# USB-Isolator_v11.net
KiCad netlist of a schematic drawn in EAGLE
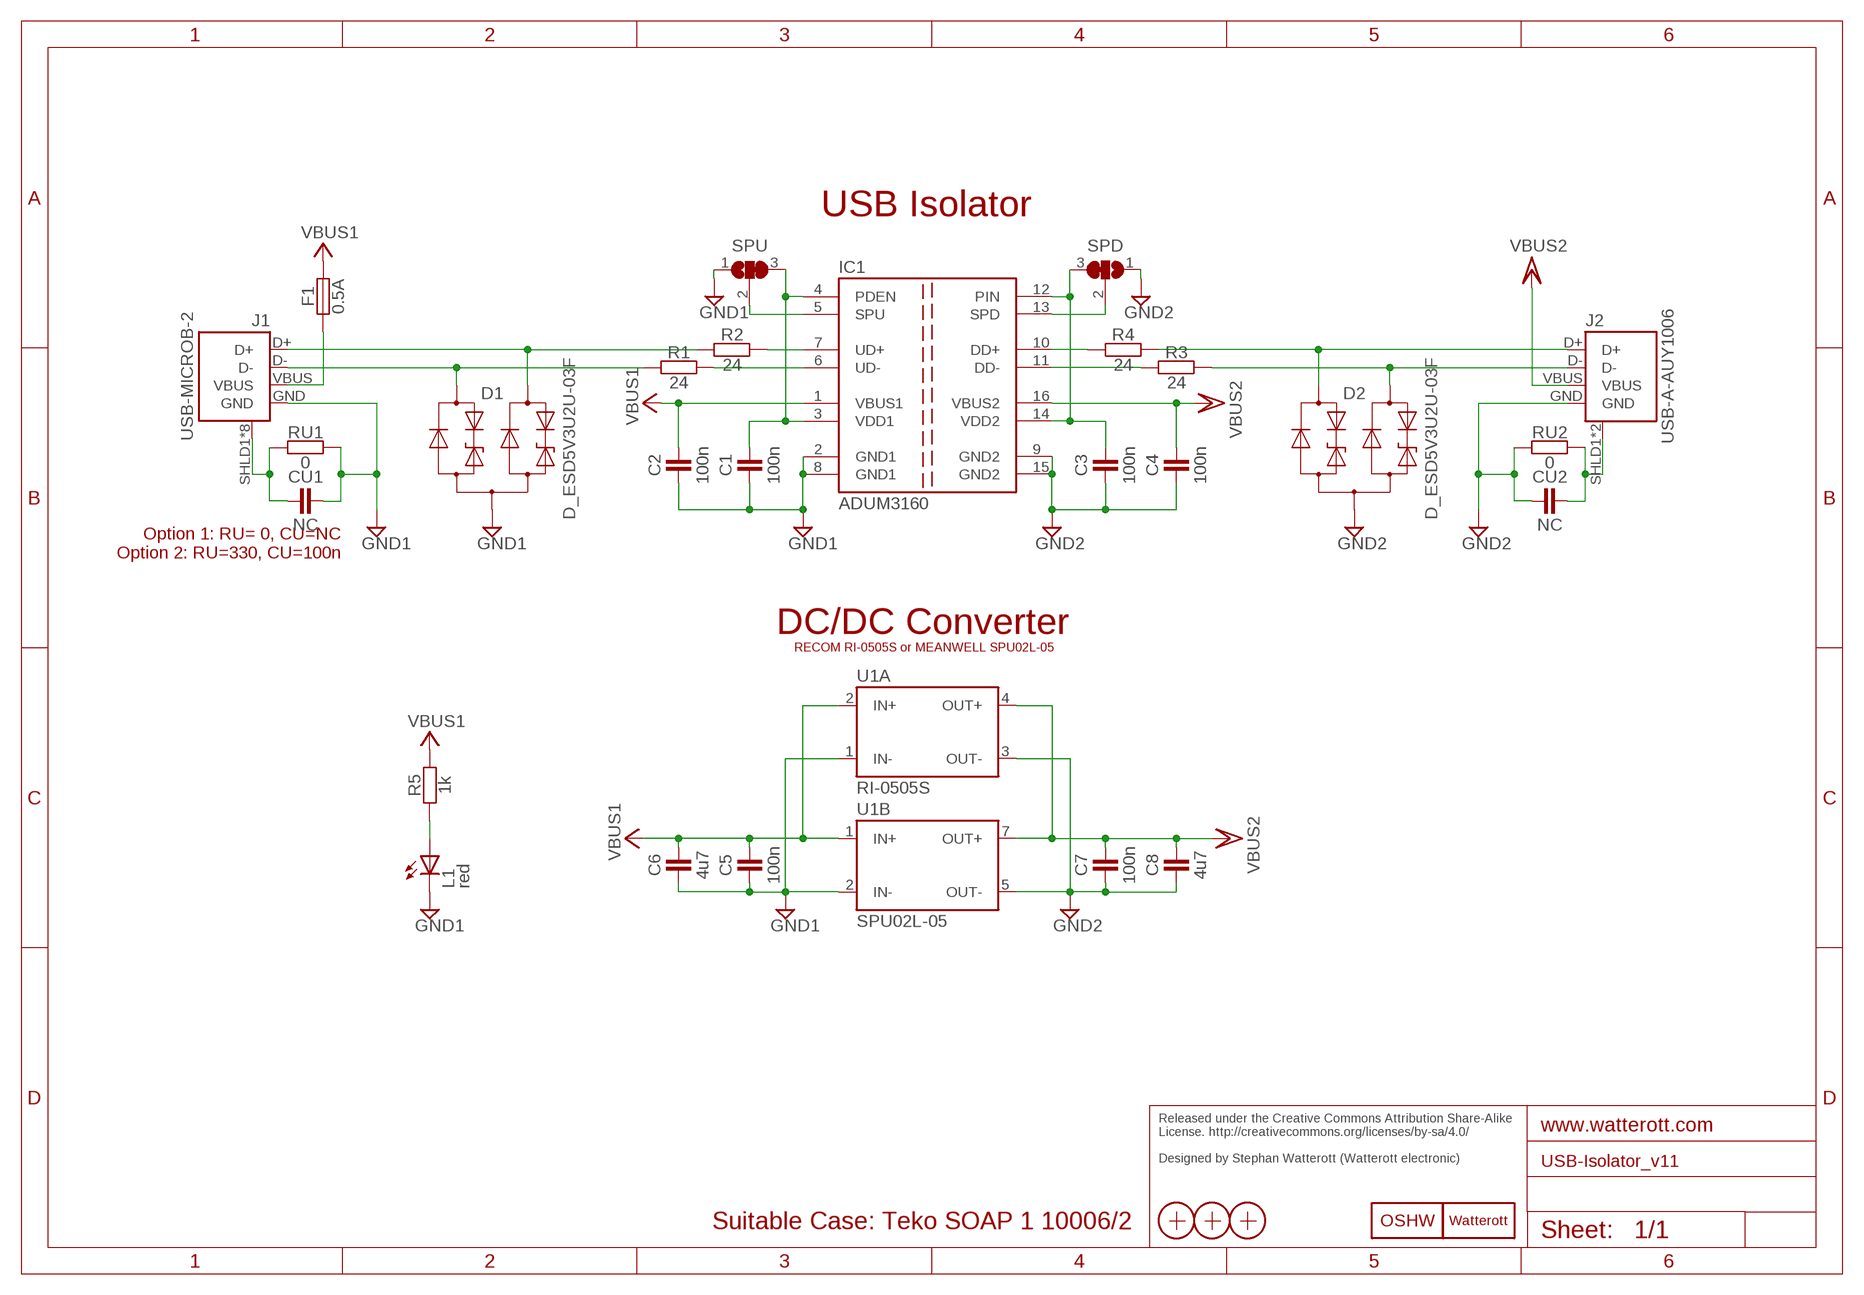
[diagram p0: schematic, sheet 1]

(export (version "E")
  (design (tool "Eeschema 10.0.6"))
  (components
    (comp (ref "C1")
      (value "100n")
      (footprint "eagle-import:C0603")
      (libsource (lib "eagle-import") (part "CAPACITOR-0603"))
    )
    (comp (ref "C2")
      (value "100n")
      (footprint "eagle-import:C0603")
      (libsource (lib "eagle-import") (part "CAPACITOR-0603"))
    )
    (comp (ref "C3")
      (value "100n")
      (footprint "eagle-import:C0603")
      (libsource (lib "eagle-import") (part "CAPACITOR-0603"))
    )
    (comp (ref "C4")
      (value "100n")
      (footprint "eagle-import:C0603")
      (libsource (lib "eagle-import") (part "CAPACITOR-0603"))
    )
    (comp (ref "C5")
      (value "100n")
      (footprint "eagle-import:C0603")
      (libsource (lib "eagle-import") (part "CAPACITOR-0603"))
    )
    (comp (ref "C6")
      (value "4u7")
      (footprint "eagle-import:C1206")
      (libsource (lib "eagle-import") (part "CAPACITOR-1206"))
    )
    (comp (ref "C7")
      (value "100n")
      (footprint "eagle-import:C0603")
      (libsource (lib "eagle-import") (part "CAPACITOR-0603"))
    )
    (comp (ref "C8")
      (value "4u7")
      (footprint "eagle-import:C1206")
      (libsource (lib "eagle-import") (part "CAPACITOR-1206"))
    )
    (comp (ref "CU1")
      (value "NC")
      (footprint "eagle-import:C0603")
      (libsource (lib "eagle-import") (part "CAPACITOR-0603"))
    )
    (comp (ref "CU2")
      (value "NC")
      (footprint "eagle-import:C0603")
      (libsource (lib "eagle-import") (part "CAPACITOR-0603"))
    )
    (comp (ref "D1")
      (value "D_ESD5V3U2U-03F")
      (footprint "eagle-import:SOT723")
      (libsource (lib "eagle-import") (part "D_ESD5V3U2U-03F"))
    )
    (comp (ref "D2")
      (value "D_ESD5V3U2U-03F")
      (footprint "eagle-import:SOT723")
      (libsource (lib "eagle-import") (part "D_ESD5V3U2U-03F"))
    )
    (comp (ref "F1")
      (value "0.5A")
      (footprint "eagle-import:C0805")
      (libsource (lib "eagle-import") (part "FUSE-0805"))
    )
    (comp (ref "IC1")
      (value "ADUM3160")
      (footprint "eagle-import:SO16W")
      (libsource (lib "eagle-import") (part "ADUM3160"))
    )
    (comp (ref "J1")
      (value "USB-MICROB-2")
      (footprint "eagle-import:USB-MICROB-10118194")
      (libsource (lib "eagle-import") (part "USB-MICROB-2"))
    )
    (comp (ref "J2")
      (value "USB-A-AUY1006")
      (footprint "eagle-import:USB-AU-Y1006-R")
      (fields (field (name "MANUFACTURER") "AU-Y1006-R"))
      (libsource (lib "eagle-import") (part "USB-A-AUY1006"))
    )
    (comp (ref "L1")
      (value "red")
      (footprint "eagle-import:C0603")
      (libsource (lib "eagle-import") (part "LED-0603"))
    )
    (comp (ref "LOGO2")
      (value "OSHW_LOGOX0070")
      (footprint "eagle-import:OSHW_6X70")
      (libsource (lib "eagle-import") (part "OSHW_LOGOX0070"))
    )
    (comp (ref "LOGO3")
      (value "LOGO-S_PLACE_M")
      (footprint "eagle-import:SPARK_TPLACE_M")
      (libsource (lib "eagle-import") (part "LOGO-S_PLACE_M"))
    )
    (comp (ref "R1")
      (value "24")
      (footprint "eagle-import:C0603")
      (libsource (lib "eagle-import") (part "RESISTOR-0603"))
    )
    (comp (ref "R2")
      (value "24")
      (footprint "eagle-import:C0603")
      (libsource (lib "eagle-import") (part "RESISTOR-0603"))
    )
    (comp (ref "R3")
      (value "24")
      (footprint "eagle-import:C0603")
      (libsource (lib "eagle-import") (part "RESISTOR-0603"))
    )
    (comp (ref "R4")
      (value "24")
      (footprint "eagle-import:C0603")
      (libsource (lib "eagle-import") (part "RESISTOR-0603"))
    )
    (comp (ref "R5")
      (value "1k")
      (footprint "eagle-import:C0603")
      (libsource (lib "eagle-import") (part "RESISTOR-0603"))
    )
    (comp (ref "RU1")
      (value "0")
      (footprint "eagle-import:C0603")
      (libsource (lib "eagle-import") (part "RESISTOR-0603"))
    )
    (comp (ref "RU2")
      (value "0")
      (footprint "eagle-import:C0603")
      (libsource (lib "eagle-import") (part "RESISTOR-0603"))
    )
    (comp (ref "SPD")
      (value "JUMPER3-0603")
      (footprint "eagle-import:JUMPER3-0603")
      (libsource (lib "eagle-import") (part "JUMPER3-0603"))
    )
    (comp (ref "SPU")
      (value "JUMPER3-0603")
      (footprint "eagle-import:JUMPER3-0603")
      (libsource (lib "eagle-import") (part "JUMPER3-0603"))
    )
    (comp (ref "U1A")
      (value "RI-0505S")
      (footprint "eagle-import:RECOM_SIP4_RI")
      (libsource (lib "eagle-import") (part "DC/DC-RI"))
    )
    (comp (ref "U1B")
      (value "SPU02L-05")
      (footprint "eagle-import:MEANWELL_SIP7_SPU02")
      (libsource (lib "eagle-import") (part "DC/DC-SPU02"))
    )
    (comp (ref "X1")
      (value "PASSER-07")
      (footprint "eagle-import:PASSER_07MM")
      (libsource (lib "eagle-import") (part "PASSER-07"))
    )
    (comp (ref "X2")
      (value "PASSER-07")
      (footprint "eagle-import:PASSER_07MM")
      (libsource (lib "eagle-import") (part "PASSER-07"))
    )
    (comp (ref "X3")
      (value "PASSER-07")
      (footprint "eagle-import:PASSER_07MM")
      (libsource (lib "eagle-import") (part "PASSER-07"))
    )
  )
  (nets
    (net (code "1") (name "GND1") (class "Default")
      (node (ref "C1") (pin "1") (pinfunction "1_1") (pintype "passive"))
      (node (ref "C2") (pin "1") (pinfunction "1_1") (pintype "passive"))
      (node (ref "C5") (pin "1") (pinfunction "1_1") (pintype "passive"))
      (node (ref "C6") (pin "1") (pinfunction "1_1") (pintype "passive"))
      (node (ref "CU1") (pin "2") (pinfunction "2_2") (pintype "passive"))
      (node (ref "D1") (pin "3") (pinfunction "A_3") (pintype "passive"))
      (node (ref "IC1") (pin "2") (pinfunction "GND1_2") (pintype "power_in"))
      (node (ref "IC1") (pin "8") (pinfunction "GND1_8") (pintype "power_in"))
      (node (ref "J1") (pin "GND") (pinfunction "GND_GND") (pintype "power_in"))
      (node (ref "L1") (pin "C") (pinfunction "C_C") (pintype "passive"))
      (node (ref "RU1") (pin "2") (pinfunction "2_2") (pintype "passive"))
      (node (ref "SPU") (pin "1") (pinfunction "1_1") (pintype "passive"))
      (node (ref "U1A") (pin "1") (pinfunction "IN-_1") (pintype "power_in"))
      (node (ref "U1B") (pin "2") (pinfunction "IN-_2") (pintype "power_in"))
    )
    (net (code "2") (name "GND2") (class "Default")
      (node (ref "C3") (pin "1") (pinfunction "1_1") (pintype "passive"))
      (node (ref "C4") (pin "1") (pinfunction "1_1") (pintype "passive"))
      (node (ref "C7") (pin "1") (pinfunction "1_1") (pintype "passive"))
      (node (ref "C8") (pin "1") (pinfunction "1_1") (pintype "passive"))
      (node (ref "CU2") (pin "1") (pinfunction "1_1") (pintype "passive"))
      (node (ref "D2") (pin "3") (pinfunction "A_3") (pintype "passive"))
      (node (ref "IC1") (pin "15") (pinfunction "GND2_15") (pintype "power_in"))
      (node (ref "IC1") (pin "9") (pinfunction "GND2_9") (pintype "power_in"))
      (node (ref "J2") (pin "GND") (pinfunction "GND_GND") (pintype "power_in"))
      (node (ref "RU2") (pin "1") (pinfunction "1_1") (pintype "passive"))
      (node (ref "SPD") (pin "1") (pinfunction "1_1") (pintype "passive"))
      (node (ref "U1A") (pin "3") (pinfunction "OUT-_3") (pintype "power_in"))
      (node (ref "U1B") (pin "5") (pinfunction "OUT-_5") (pintype "power_in"))
    )
    (net (code "3") (name "Net-(CU1-Pad1)") (class "Default")
      (node (ref "CU1") (pin "1") (pinfunction "1_1") (pintype "passive"))
      (node (ref "J1") (pin "SHLD1") (pinfunction "SHIELD_SHLD1") (pintype "passive"))
      (node (ref "J1") (pin "SHLD2") (pinfunction "SHIELD_SHLD2") (pintype "passive"))
      (node (ref "J1") (pin "SHLD3") (pinfunction "SHIELD_SHLD3") (pintype "passive"))
      (node (ref "J1") (pin "SHLD4") (pinfunction "SHIELD_SHLD4") (pintype "passive"))
      (node (ref "J1") (pin "SHLD5") (pinfunction "SHIELD_SHLD5") (pintype "passive"))
      (node (ref "J1") (pin "SHLD6") (pinfunction "SHIELD_SHLD6") (pintype "passive"))
      (node (ref "J1") (pin "SHLD7") (pinfunction "SHIELD_SHLD7") (pintype "passive"))
      (node (ref "J1") (pin "SHLD8") (pinfunction "SHIELD_SHLD8") (pintype "passive"))
      (node (ref "RU1") (pin "1") (pinfunction "1_1") (pintype "passive"))
    )
    (net (code "4") (name "Net-(CU2-Pad2)") (class "Default")
      (node (ref "CU2") (pin "2") (pinfunction "2_2") (pintype "passive"))
      (node (ref "J2") (pin "SHLD1") (pinfunction "SHIELD_SHLD1") (pintype "passive"))
      (node (ref "J2") (pin "SHLD2") (pinfunction "SHIELD_SHLD2") (pintype "passive"))
      (node (ref "RU2") (pin "2") (pinfunction "2_2") (pintype "passive"))
    )
    (net (code "5") (name "Net-(D1-C1)") (class "Default")
      (node (ref "D1") (pin "1") (pinfunction "C1_1") (pintype "passive"))
      (node (ref "J1") (pin "D-") (pinfunction "D-_D-") (pintype "bidirectional"))
      (node (ref "R1") (pin "1") (pinfunction "1_1") (pintype "passive"))
    )
    (net (code "6") (name "Net-(D1-C2)") (class "Default")
      (node (ref "D1") (pin "2") (pinfunction "C2_2") (pintype "passive"))
      (node (ref "J1") (pin "D+") (pinfunction "D+_D+") (pintype "bidirectional"))
      (node (ref "R2") (pin "1") (pinfunction "1_1") (pintype "passive"))
    )
    (net (code "7") (name "Net-(D2-C1)") (class "Default")
      (node (ref "D2") (pin "1") (pinfunction "C1_1") (pintype "passive"))
      (node (ref "J2") (pin "D+") (pinfunction "D+_D+") (pintype "bidirectional"))
      (node (ref "R4") (pin "2") (pinfunction "2_2") (pintype "passive"))
    )
    (net (code "8") (name "Net-(D2-C2)") (class "Default")
      (node (ref "D2") (pin "2") (pinfunction "C2_2") (pintype "passive"))
      (node (ref "J2") (pin "D-") (pinfunction "D-_D-") (pintype "bidirectional"))
      (node (ref "R3") (pin "2") (pinfunction "2_2") (pintype "passive"))
    )
    (net (code "9") (name "Net-(F1-Pad1)") (class "Default")
      (node (ref "F1") (pin "1") (pinfunction "1_1") (pintype "passive"))
      (node (ref "J1") (pin "VBUS") (pinfunction "VBUS_VBUS") (pintype "power_in"))
    )
    (net (code "10") (name "Net-(IC1-DD+)") (class "Default")
      (node (ref "IC1") (pin "10") (pinfunction "DD+_10") (pintype "bidirectional"))
      (node (ref "R4") (pin "1") (pinfunction "1_1") (pintype "passive"))
    )
    (net (code "11") (name "Net-(IC1-DD-)") (class "Default")
      (node (ref "IC1") (pin "11") (pinfunction "DD-_11") (pintype "bidirectional"))
      (node (ref "R3") (pin "1") (pinfunction "1_1") (pintype "passive"))
    )
    (net (code "12") (name "Net-(IC1-PDEN)") (class "Default")
      (node (ref "C1") (pin "2") (pinfunction "2_2") (pintype "passive"))
      (node (ref "IC1") (pin "3") (pinfunction "VDD1_3") (pintype "power_in"))
      (node (ref "IC1") (pin "4") (pinfunction "PDEN_4") (pintype "input"))
      (node (ref "SPU") (pin "3") (pinfunction "3_3") (pintype "passive"))
    )
    (net (code "13") (name "Net-(IC1-PIN)") (class "Default")
      (node (ref "C3") (pin "2") (pinfunction "2_2") (pintype "passive"))
      (node (ref "IC1") (pin "12") (pinfunction "PIN_12") (pintype "input"))
      (node (ref "IC1") (pin "14") (pinfunction "VDD2_14") (pintype "power_in"))
      (node (ref "SPD") (pin "3") (pinfunction "3_3") (pintype "passive"))
    )
    (net (code "14") (name "Net-(IC1-SPD)") (class "Default")
      (node (ref "IC1") (pin "13") (pinfunction "SPD_13") (pintype "input"))
      (node (ref "SPD") (pin "2") (pinfunction "2_2") (pintype "passive"))
    )
    (net (code "15") (name "Net-(IC1-SPU)") (class "Default")
      (node (ref "IC1") (pin "5") (pinfunction "SPU_5") (pintype "input"))
      (node (ref "SPU") (pin "2") (pinfunction "2_2") (pintype "passive"))
    )
    (net (code "16") (name "Net-(IC1-UD+)") (class "Default")
      (node (ref "IC1") (pin "7") (pinfunction "UD+_7") (pintype "bidirectional"))
      (node (ref "R2") (pin "2") (pinfunction "2_2") (pintype "passive"))
    )
    (net (code "17") (name "Net-(IC1-UD-)") (class "Default")
      (node (ref "IC1") (pin "6") (pinfunction "UD-_6") (pintype "bidirectional"))
      (node (ref "R1") (pin "2") (pinfunction "2_2") (pintype "passive"))
    )
    (net (code "18") (name "Net-(L1-PadA)") (class "Default")
      (node (ref "L1") (pin "A") (pinfunction "A_A") (pintype "passive"))
      (node (ref "R5") (pin "1") (pinfunction "1_1") (pintype "passive"))
    )
    (net (code "19") (name "VBUS1") (class "Default")
      (node (ref "C2") (pin "2") (pinfunction "2_2") (pintype "passive"))
      (node (ref "C5") (pin "2") (pinfunction "2_2") (pintype "passive"))
      (node (ref "C6") (pin "2") (pinfunction "2_2") (pintype "passive"))
      (node (ref "F1") (pin "2") (pinfunction "2_2") (pintype "passive"))
      (node (ref "IC1") (pin "1") (pinfunction "VBUS1_1") (pintype "power_in"))
      (node (ref "R5") (pin "2") (pinfunction "2_2") (pintype "passive"))
      (node (ref "U1A") (pin "2") (pinfunction "IN+_2") (pintype "power_in"))
      (node (ref "U1B") (pin "1") (pinfunction "IN+_1") (pintype "power_in"))
    )
    (net (code "20") (name "VBUS2") (class "Default")
      (node (ref "C4") (pin "2") (pinfunction "2_2") (pintype "passive"))
      (node (ref "C7") (pin "2") (pinfunction "2_2") (pintype "passive"))
      (node (ref "C8") (pin "2") (pinfunction "2_2") (pintype "passive"))
      (node (ref "IC1") (pin "16") (pinfunction "VBUS2_16") (pintype "power_in"))
      (node (ref "J2") (pin "VBUS") (pinfunction "VBUS_VBUS") (pintype "power_in"))
      (node (ref "U1A") (pin "4") (pinfunction "OUT+_4") (pintype "power_in"))
      (node (ref "U1B") (pin "7") (pinfunction "OUT+_7") (pintype "power_in"))
    )
  )
)
